# Adafruit_Flora_TSL2561_Lux.net
KiCad netlist of a schematic drawn in EAGLE
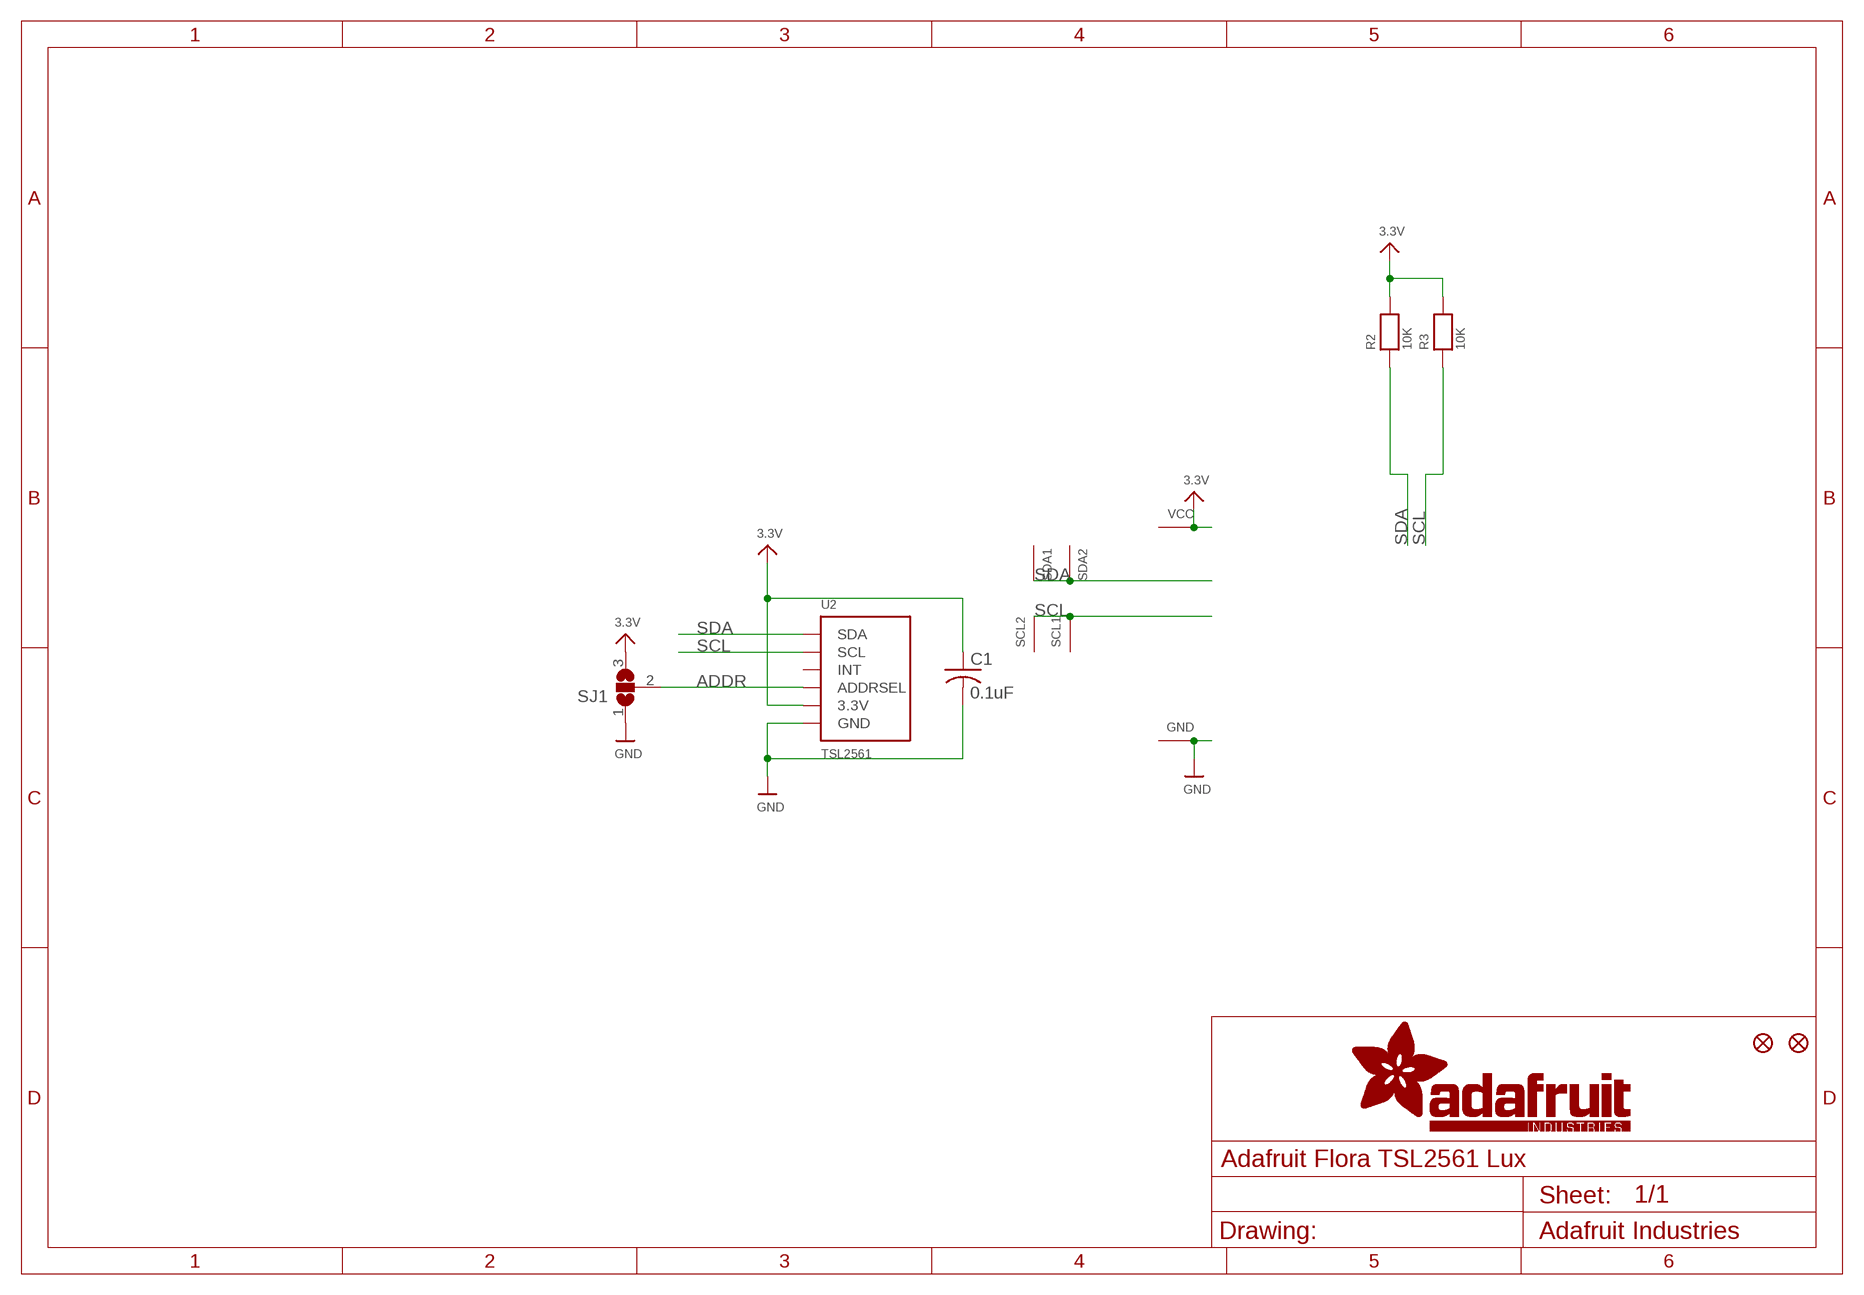
[diagram p0: schematic, sheet 1]

(export (version "E")
  (design (tool "Eeschema 10.0.6"))
  (components
    (comp (ref "C1")
      (value "0.1uF")
      (footprint "eagle-import:C0805K")
      (libsource (lib "eagle-import") (part "C-USC0805K"))
    )
    (comp (ref "FID1")
      (value "FIDUCIAL\"\"")
      (footprint "eagle-import:FIDUCIAL_1MM")
      (libsource (lib "eagle-import") (part "FIDUCIAL{dblquote}{dblquote}"))
    )
    (comp (ref "FID2")
      (value "FIDUCIAL\"\"")
      (footprint "eagle-import:FIDUCIAL_1MM")
      (libsource (lib "eagle-import") (part "FIDUCIAL{dblquote}{dblquote}"))
    )
    (comp (ref "GND")
      (value "SEWTAP0.5IN")
      (footprint "eagle-import:SEWINGTAP_0.5")
      (libsource (lib "eagle-import") (part "SEWTAP0.5IN"))
    )
    (comp (ref "R2")
      (value "10K")
      (footprint "eagle-import:_0805")
      (libsource (lib "eagle-import") (part "RESISTOR_0805"))
    )
    (comp (ref "R3")
      (value "10K")
      (footprint "eagle-import:_0805")
      (libsource (lib "eagle-import") (part "RESISTOR_0805"))
    )
    (comp (ref "SCL1")
      (value "SEWTAP0.5IN")
      (footprint "eagle-import:SEWINGTAP_0.5")
      (libsource (lib "eagle-import") (part "SEWTAP0.5IN"))
    )
    (comp (ref "SCL2")
      (value "SEWTAP0.5IN")
      (footprint "eagle-import:SEWINGTAP_0.5")
      (libsource (lib "eagle-import") (part "SEWTAP0.5IN"))
    )
    (comp (ref "SDA1")
      (value "SEWTAP0.5IN")
      (footprint "eagle-import:SEWINGTAP_0.5")
      (libsource (lib "eagle-import") (part "SEWTAP0.5IN"))
    )
    (comp (ref "SDA2")
      (value "SEWTAP0.5IN")
      (footprint "eagle-import:SEWINGTAP_0.5")
      (libsource (lib "eagle-import") (part "SEWTAP0.5IN"))
    )
    (comp (ref "SJ1")
      (value "SJ2W")
      (footprint "eagle-import:SJ_2")
      (libsource (lib "eagle-import") (part "SJ2W"))
    )
    (comp (ref "U2")
      (value "TSL2561")
      (footprint "eagle-import:TSL2561_FN")
      (libsource (lib "eagle-import") (part "TSL2561"))
    )
    (comp (ref "VCC")
      (value "SEWTAP0.5IN")
      (footprint "eagle-import:SEWINGTAP_0.5")
      (libsource (lib "eagle-import") (part "SEWTAP0.5IN"))
    )
  )
  (nets
    (net (code "1") (name "/ADDR") (class "Default")
      (node (ref "SJ1") (pin "2") (pinfunction "2_2") (pintype "passive"))
      (node (ref "U2") (pin "ADR") (pinfunction "ADDRSEL_ADR") (pintype "bidirectional"))
    )
    (net (code "2") (name "/SCL") (class "Default")
      (node (ref "R3") (pin "1") (pinfunction "1_1") (pintype "passive"))
      (node (ref "SCL1") (pin "TAP") (pinfunction "SEW_TAP") (pintype "bidirectional"))
      (node (ref "SCL2") (pin "TAP") (pinfunction "SEW_TAP") (pintype "bidirectional"))
      (node (ref "U2") (pin "CLK") (pinfunction "SCL_CLK") (pintype "bidirectional"))
    )
    (net (code "3") (name "/SDA") (class "Default")
      (node (ref "R2") (pin "1") (pinfunction "1_1") (pintype "passive"))
      (node (ref "SDA1") (pin "TAP") (pinfunction "SEW_TAP") (pintype "bidirectional"))
      (node (ref "SDA2") (pin "TAP") (pinfunction "SEW_TAP") (pintype "bidirectional"))
      (node (ref "U2") (pin "DATA") (pinfunction "SDA_DATA") (pintype "bidirectional"))
    )
    (net (code "4") (name "3.3V") (class "Default")
      (node (ref "C1") (pin "1") (pinfunction "1_1") (pintype "passive"))
      (node (ref "R2") (pin "2") (pinfunction "2_2") (pintype "passive"))
      (node (ref "R3") (pin "2") (pinfunction "2_2") (pintype "passive"))
      (node (ref "SJ1") (pin "3") (pinfunction "3_3") (pintype "passive"))
      (node (ref "U2") (pin "VDD") (pinfunction "3.3V_VDD") (pintype "bidirectional"))
      (node (ref "VCC") (pin "TAP") (pinfunction "SEW_TAP") (pintype "bidirectional"))
    )
    (net (code "5") (name "GND") (class "Default")
      (node (ref "C1") (pin "2") (pinfunction "2_2") (pintype "passive"))
      (node (ref "GND") (pin "TAP") (pinfunction "SEW_TAP") (pintype "bidirectional"))
      (node (ref "SJ1") (pin "1") (pinfunction "1_1") (pintype "passive"))
      (node (ref "U2") (pin "VSS") (pinfunction "GND_VSS") (pintype "bidirectional"))
    )
    (net (code "6") (name "unconnected-(U2-PadINT)") (class "Default")
      (node (ref "U2") (pin "INT") (pinfunction "INT_INT") (pintype "bidirectional"))
    )
  )
)
